# Stepper_Motor_Driver_v1_1.net
KiCad netlist of a schematic drawn in EAGLE
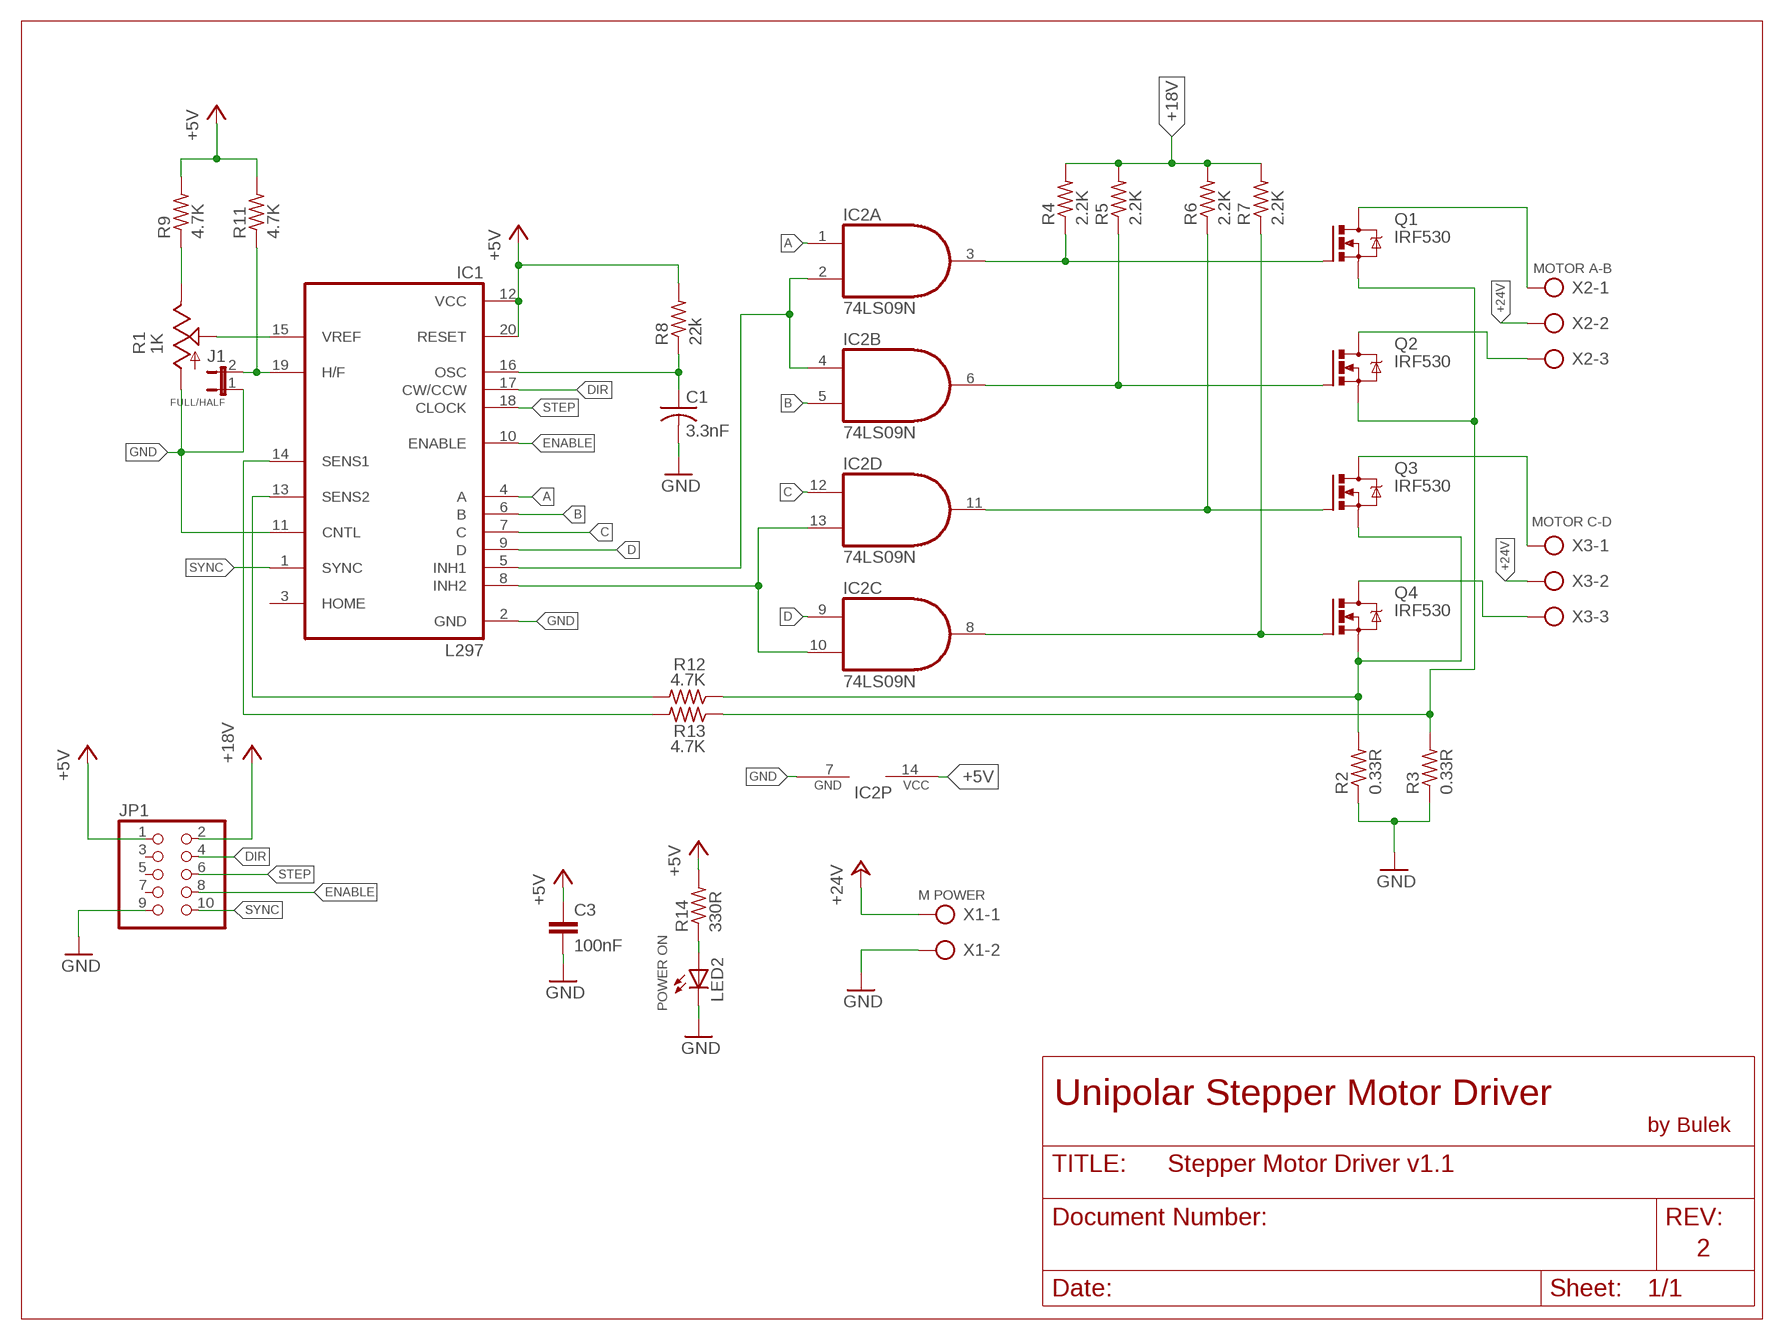
[diagram p0: schematic, sheet 1]

(export (version "E")
  (design (tool "Eeschema 10.0.6"))
  (components
    (comp (ref "C1")
      (value "3.3nF")
      (footprint "eagle-import:C025-024X044")
      (libsource (lib "eagle-import") (part "C-US025-024X044"))
    )
    (comp (ref "C3")
      (value "100nF")
      (footprint "eagle-import:C025-025X050")
      (libsource (lib "eagle-import") (part "C-EU025-025X050"))
    )
    (comp (ref "FULL/HALF")
      (value "J1")
      (footprint "eagle-import:JP1")
      (libsource (lib "eagle-import") (part "JP1E"))
    )
    (comp (ref "IC1")
      (value "L297")
      (footprint "eagle-import:DIL20")
      (fields (field (name "MPN") "L297/1"))
      (libsource (lib "eagle-import") (part "L297"))
    )
    (comp (ref "IC2")
      (value "74LS09N")
      (footprint "eagle-import:DIL14")
      (libsource (lib "eagle-import") (part "7409NLS"))
    )
    (comp (ref "JP1")
      (value "PINHD-2X5")
      (footprint "eagle-import:2X05")
      (libsource (lib "eagle-import") (part "PINHD-2X5"))
    )
    (comp (ref "LED2")
      (value "POWER ON")
      (footprint "eagle-import:LED5MM")
      (libsource (lib "eagle-import") (part "LED5MM"))
    )
    (comp (ref "Q1")
      (value "IRF530")
      (footprint "eagle-import:TO220BV")
      (libsource (lib "eagle-import") (part "IRF530"))
    )
    (comp (ref "Q2")
      (value "IRF530")
      (footprint "eagle-import:TO220BV")
      (libsource (lib "eagle-import") (part "IRF530"))
    )
    (comp (ref "Q3")
      (value "IRF530")
      (footprint "eagle-import:TO220BV")
      (libsource (lib "eagle-import") (part "IRF530"))
    )
    (comp (ref "Q4")
      (value "IRF530")
      (footprint "eagle-import:TO220BV")
      (libsource (lib "eagle-import") (part "IRF530"))
    )
    (comp (ref "R1")
      (value "1K")
      (footprint "eagle-import:S63X")
      (libsource (lib "eagle-import") (part "TRIM_US-S63X"))
    )
    (comp (ref "R2")
      (value "0.33R")
      (footprint "eagle-import:0617_22")
      (libsource (lib "eagle-import") (part "R-US_0617/22"))
    )
    (comp (ref "R3")
      (value "0.33R")
      (footprint "eagle-import:0617_22")
      (libsource (lib "eagle-import") (part "R-US_0617/22"))
    )
    (comp (ref "R4")
      (value "2.2K")
      (footprint "eagle-import:0207_10")
      (libsource (lib "eagle-import") (part "R-US_0207/10"))
    )
    (comp (ref "R5")
      (value "2.2K")
      (footprint "eagle-import:0207_10")
      (libsource (lib "eagle-import") (part "R-US_0207/10"))
    )
    (comp (ref "R6")
      (value "2.2K")
      (footprint "eagle-import:0207_10")
      (libsource (lib "eagle-import") (part "R-US_0207/10"))
    )
    (comp (ref "R7")
      (value "2.2K")
      (footprint "eagle-import:0207_10")
      (libsource (lib "eagle-import") (part "R-US_0207/10"))
    )
    (comp (ref "R8")
      (value "22k")
      (footprint "eagle-import:0207_10")
      (libsource (lib "eagle-import") (part "R-US_0207/10"))
    )
    (comp (ref "R9")
      (value "4.7K")
      (footprint "eagle-import:0207_10")
      (libsource (lib "eagle-import") (part "R-US_0207/10"))
    )
    (comp (ref "R11")
      (value "4.7K")
      (footprint "eagle-import:0207_10")
      (libsource (lib "eagle-import") (part "R-US_0207/10"))
    )
    (comp (ref "R12")
      (value "4.7K")
      (footprint "eagle-import:0207_10")
      (libsource (lib "eagle-import") (part "R-US_0207/10"))
    )
    (comp (ref "R13")
      (value "4.7K")
      (footprint "eagle-import:0207_10")
      (libsource (lib "eagle-import") (part "R-US_0207/10"))
    )
    (comp (ref "R14")
      (value "330R")
      (footprint "eagle-import:0207_10")
      (libsource (lib "eagle-import") (part "R-US_0207/10"))
    )
    (comp (ref "X1")
      (value "M POWER")
      (footprint "eagle-import:AK300_2")
      (libsource (lib "eagle-import") (part "AK300/2"))
    )
    (comp (ref "X2")
      (value "MOTOR A-B")
      (footprint "eagle-import:AK300_3")
      (libsource (lib "eagle-import") (part "AK300/3"))
    )
    (comp (ref "X3")
      (value "MOTOR C-D")
      (footprint "eagle-import:AK300_3")
      (libsource (lib "eagle-import") (part "AK300/3"))
    )
  )
  (nets
    (net (code "1") (name "+5V") (class "Default")
      (node (ref "C3") (pin "1") (pinfunction "1_1") (pintype "passive"))
      (node (ref "IC1") (pin "12") (pinfunction "VCC_12") (pintype "power_in"))
      (node (ref "IC1") (pin "20") (pinfunction "RESET_20") (pintype "input"))
      (node (ref "IC2") (pin "14") (pinfunction "VCC_14") (pintype "power_in"))
      (node (ref "JP1") (pin "1") (pinfunction "1_1") (pintype "passive"))
      (node (ref "R11") (pin "2") (pinfunction "2_2") (pintype "passive"))
      (node (ref "R14") (pin "2") (pinfunction "2_2") (pintype "passive"))
      (node (ref "R8") (pin "2") (pinfunction "2_2") (pintype "passive"))
      (node (ref "R9") (pin "2") (pinfunction "2_2") (pintype "passive"))
    )
    (net (code "2") (name "+18V") (class "Default")
      (node (ref "JP1") (pin "2") (pinfunction "2_2") (pintype "passive"))
      (node (ref "R4") (pin "2") (pinfunction "2_2") (pintype "passive"))
      (node (ref "R5") (pin "2") (pinfunction "2_2") (pintype "passive"))
      (node (ref "R6") (pin "2") (pinfunction "2_2") (pintype "passive"))
      (node (ref "R7") (pin "2") (pinfunction "2_2") (pintype "passive"))
    )
    (net (code "3") (name "+24V") (class "Default")
      (node (ref "X1") (pin "1") (pinfunction "KL_1") (pintype "passive"))
      (node (ref "X2") (pin "2") (pinfunction "KL_2") (pintype "passive"))
      (node (ref "X3") (pin "2") (pinfunction "KL_2") (pintype "passive"))
    )
    (net (code "4") (name "A") (class "Default")
      (node (ref "IC1") (pin "4") (pinfunction "A_4") (pintype "output"))
      (node (ref "IC2") (pin "1") (pinfunction "I0_1") (pintype "input"))
    )
    (net (code "5") (name "B") (class "Default")
      (node (ref "IC1") (pin "6") (pinfunction "B_6") (pintype "output"))
      (node (ref "IC2") (pin "5") (pinfunction "I1_5") (pintype "input"))
    )
    (net (code "6") (name "C") (class "Default")
      (node (ref "IC1") (pin "7") (pinfunction "C_7") (pintype "output"))
      (node (ref "IC2") (pin "12") (pinfunction "I0_12") (pintype "input"))
    )
    (net (code "7") (name "D") (class "Default")
      (node (ref "IC1") (pin "9") (pinfunction "D_9") (pintype "output"))
      (node (ref "IC2") (pin "9") (pinfunction "I0_9") (pintype "input"))
    )
    (net (code "8") (name "DIR") (class "Default")
      (node (ref "IC1") (pin "17") (pinfunction "CW/CCW_17") (pintype "input"))
      (node (ref "JP1") (pin "4") (pinfunction "4_4") (pintype "passive"))
    )
    (net (code "9") (name "ENABLE") (class "Default")
      (node (ref "IC1") (pin "10") (pinfunction "ENABLE_10") (pintype "input"))
      (node (ref "JP1") (pin "8") (pinfunction "8_8") (pintype "passive"))
    )
    (net (code "10") (name "GND") (class "Default")
      (node (ref "C1") (pin "2") (pinfunction "2_2") (pintype "passive"))
      (node (ref "C3") (pin "2") (pinfunction "2_2") (pintype "passive"))
      (node (ref "FULL/HALF") (pin "1") (pinfunction "1_1") (pintype "passive"))
      (node (ref "IC1") (pin "11") (pinfunction "CNTL_11") (pintype "input"))
      (node (ref "IC1") (pin "2") (pinfunction "GND_2") (pintype "power_in"))
      (node (ref "IC2") (pin "7") (pinfunction "GND_7") (pintype "power_in"))
      (node (ref "JP1") (pin "9") (pinfunction "9_9") (pintype "passive"))
      (node (ref "LED2") (pin "K") (pinfunction "C_K") (pintype "passive"))
      (node (ref "R1") (pin "A") (pinfunction "A_A") (pintype "passive"))
      (node (ref "R2") (pin "1") (pinfunction "1_1") (pintype "passive"))
      (node (ref "R3") (pin "1") (pinfunction "1_1") (pintype "passive"))
      (node (ref "X1") (pin "2") (pinfunction "KL_2") (pintype "passive"))
    )
    (net (code "11") (name "Net-(IC1-H{slash}F)") (class "Default")
      (node (ref "FULL/HALF") (pin "2") (pinfunction "2_2") (pintype "passive"))
      (node (ref "IC1") (pin "19") (pinfunction "H/F_19") (pintype "input"))
      (node (ref "R11") (pin "1") (pinfunction "1_1") (pintype "passive"))
    )
    (net (code "12") (name "Net-(IC1-INH1)") (class "Default")
      (node (ref "IC1") (pin "5") (pinfunction "INH1_5") (pintype "output"))
      (node (ref "IC2") (pin "2") (pinfunction "I1_2") (pintype "input"))
      (node (ref "IC2") (pin "4") (pinfunction "I0_4") (pintype "input"))
    )
    (net (code "13") (name "Net-(IC1-INH2)") (class "Default")
      (node (ref "IC1") (pin "8") (pinfunction "INH2_8") (pintype "output"))
      (node (ref "IC2") (pin "10") (pinfunction "I1_10") (pintype "input"))
      (node (ref "IC2") (pin "13") (pinfunction "I1_13") (pintype "input"))
    )
    (net (code "14") (name "Net-(IC1-OSC)") (class "Default")
      (node (ref "C1") (pin "1") (pinfunction "1_1") (pintype "passive"))
      (node (ref "IC1") (pin "16") (pinfunction "OSC_16") (pintype "bidirectional"))
      (node (ref "R8") (pin "1") (pinfunction "1_1") (pintype "passive"))
    )
    (net (code "15") (name "Net-(IC1-SENS1)") (class "Default")
      (node (ref "IC1") (pin "14") (pinfunction "SENS1_14") (pintype "output"))
      (node (ref "R13") (pin "2") (pinfunction "2_2") (pintype "passive"))
    )
    (net (code "16") (name "Net-(IC1-SENS2)") (class "Default")
      (node (ref "IC1") (pin "13") (pinfunction "SENS2_13") (pintype "output"))
      (node (ref "R12") (pin "2") (pinfunction "2_2") (pintype "passive"))
    )
    (net (code "17") (name "Net-(IC1-VREF)") (class "Default")
      (node (ref "IC1") (pin "15") (pinfunction "VREF_15") (pintype "input"))
      (node (ref "R1") (pin "S") (pinfunction "S_S") (pintype "passive"))
    )
    (net (code "18") (name "Net-(IC2A-O)") (class "Default")
      (node (ref "IC2") (pin "3") (pinfunction "O_3") (pintype "open_collector"))
      (node (ref "Q1") (pin "G") (pinfunction "G_G") (pintype "passive"))
      (node (ref "R4") (pin "1") (pinfunction "1_1") (pintype "passive"))
    )
    (net (code "19") (name "Net-(IC2B-O)") (class "Default")
      (node (ref "IC2") (pin "6") (pinfunction "O_6") (pintype "open_collector"))
      (node (ref "Q2") (pin "G") (pinfunction "G_G") (pintype "passive"))
      (node (ref "R5") (pin "1") (pinfunction "1_1") (pintype "passive"))
    )
    (net (code "20") (name "Net-(IC2C-O)") (class "Default")
      (node (ref "IC2") (pin "8") (pinfunction "O_8") (pintype "open_collector"))
      (node (ref "Q4") (pin "G") (pinfunction "G_G") (pintype "passive"))
      (node (ref "R7") (pin "1") (pinfunction "1_1") (pintype "passive"))
    )
    (net (code "21") (name "Net-(IC2D-O)") (class "Default")
      (node (ref "IC2") (pin "11") (pinfunction "O_11") (pintype "open_collector"))
      (node (ref "Q3") (pin "G") (pinfunction "G_G") (pintype "passive"))
      (node (ref "R6") (pin "1") (pinfunction "1_1") (pintype "passive"))
    )
    (net (code "22") (name "Net-(LED2-PadA)") (class "Default")
      (node (ref "LED2") (pin "A") (pinfunction "A_A") (pintype "passive"))
      (node (ref "R14") (pin "1") (pinfunction "1_1") (pintype "passive"))
    )
    (net (code "23") (name "Net-(Q1-PadS)") (class "Default")
      (node (ref "Q1") (pin "S") (pinfunction "S_S") (pintype "passive"))
      (node (ref "Q2") (pin "S") (pinfunction "S_S") (pintype "passive"))
      (node (ref "R13") (pin "1") (pinfunction "1_1") (pintype "passive"))
      (node (ref "R3") (pin "2") (pinfunction "2_2") (pintype "passive"))
    )
    (net (code "24") (name "Net-(Q3-PadS)") (class "Default")
      (node (ref "Q3") (pin "S") (pinfunction "S_S") (pintype "passive"))
      (node (ref "Q4") (pin "S") (pinfunction "S_S") (pintype "passive"))
      (node (ref "R12") (pin "1") (pinfunction "1_1") (pintype "passive"))
      (node (ref "R2") (pin "2") (pinfunction "2_2") (pintype "passive"))
    )
    (net (code "25") (name "Net-(R1-PadE)") (class "Default")
      (node (ref "R1") (pin "E") (pinfunction "E_E") (pintype "passive"))
      (node (ref "R9") (pin "1") (pinfunction "1_1") (pintype "passive"))
    )
    (net (code "26") (name "Net-(X2A-KL)") (class "Default")
      (node (ref "Q1") (pin "D") (pinfunction "D_D") (pintype "passive"))
      (node (ref "X2") (pin "1") (pinfunction "KL_1") (pintype "passive"))
    )
    (net (code "27") (name "Net-(X2C-KL)") (class "Default")
      (node (ref "Q2") (pin "D") (pinfunction "D_D") (pintype "passive"))
      (node (ref "X2") (pin "3") (pinfunction "KL_3") (pintype "passive"))
    )
    (net (code "28") (name "Net-(X3A-KL)") (class "Default")
      (node (ref "Q3") (pin "D") (pinfunction "D_D") (pintype "passive"))
      (node (ref "X3") (pin "1") (pinfunction "KL_1") (pintype "passive"))
    )
    (net (code "29") (name "Net-(X3C-KL)") (class "Default")
      (node (ref "Q4") (pin "D") (pinfunction "D_D") (pintype "passive"))
      (node (ref "X3") (pin "3") (pinfunction "KL_3") (pintype "passive"))
    )
    (net (code "30") (name "STEP") (class "Default")
      (node (ref "IC1") (pin "18") (pinfunction "CLOCK_18") (pintype "input"))
      (node (ref "JP1") (pin "6") (pinfunction "6_6") (pintype "passive"))
    )
    (net (code "31") (name "SYNC") (class "Default")
      (node (ref "IC1") (pin "1") (pinfunction "SYNC_1") (pintype "output"))
      (node (ref "JP1") (pin "10") (pinfunction "10_10") (pintype "passive"))
    )
    (net (code "32") (name "unconnected-(IC1-HOME-Pad3)") (class "Default")
      (node (ref "IC1") (pin "3") (pinfunction "HOME_3") (pintype "output"))
    )
    (net (code "33") (name "unconnected-(JP1-Pad3)") (class "Default")
      (node (ref "JP1") (pin "3") (pinfunction "3_3") (pintype "passive"))
    )
    (net (code "34") (name "unconnected-(JP1-Pad5)") (class "Default")
      (node (ref "JP1") (pin "5") (pinfunction "5_5") (pintype "passive"))
    )
    (net (code "35") (name "unconnected-(JP1-Pad7)") (class "Default")
      (node (ref "JP1") (pin "7") (pinfunction "7_7") (pintype "passive"))
    )
  )
)
